# MBR.net
KiCad netlist of a schematic drawn in Altium Designer
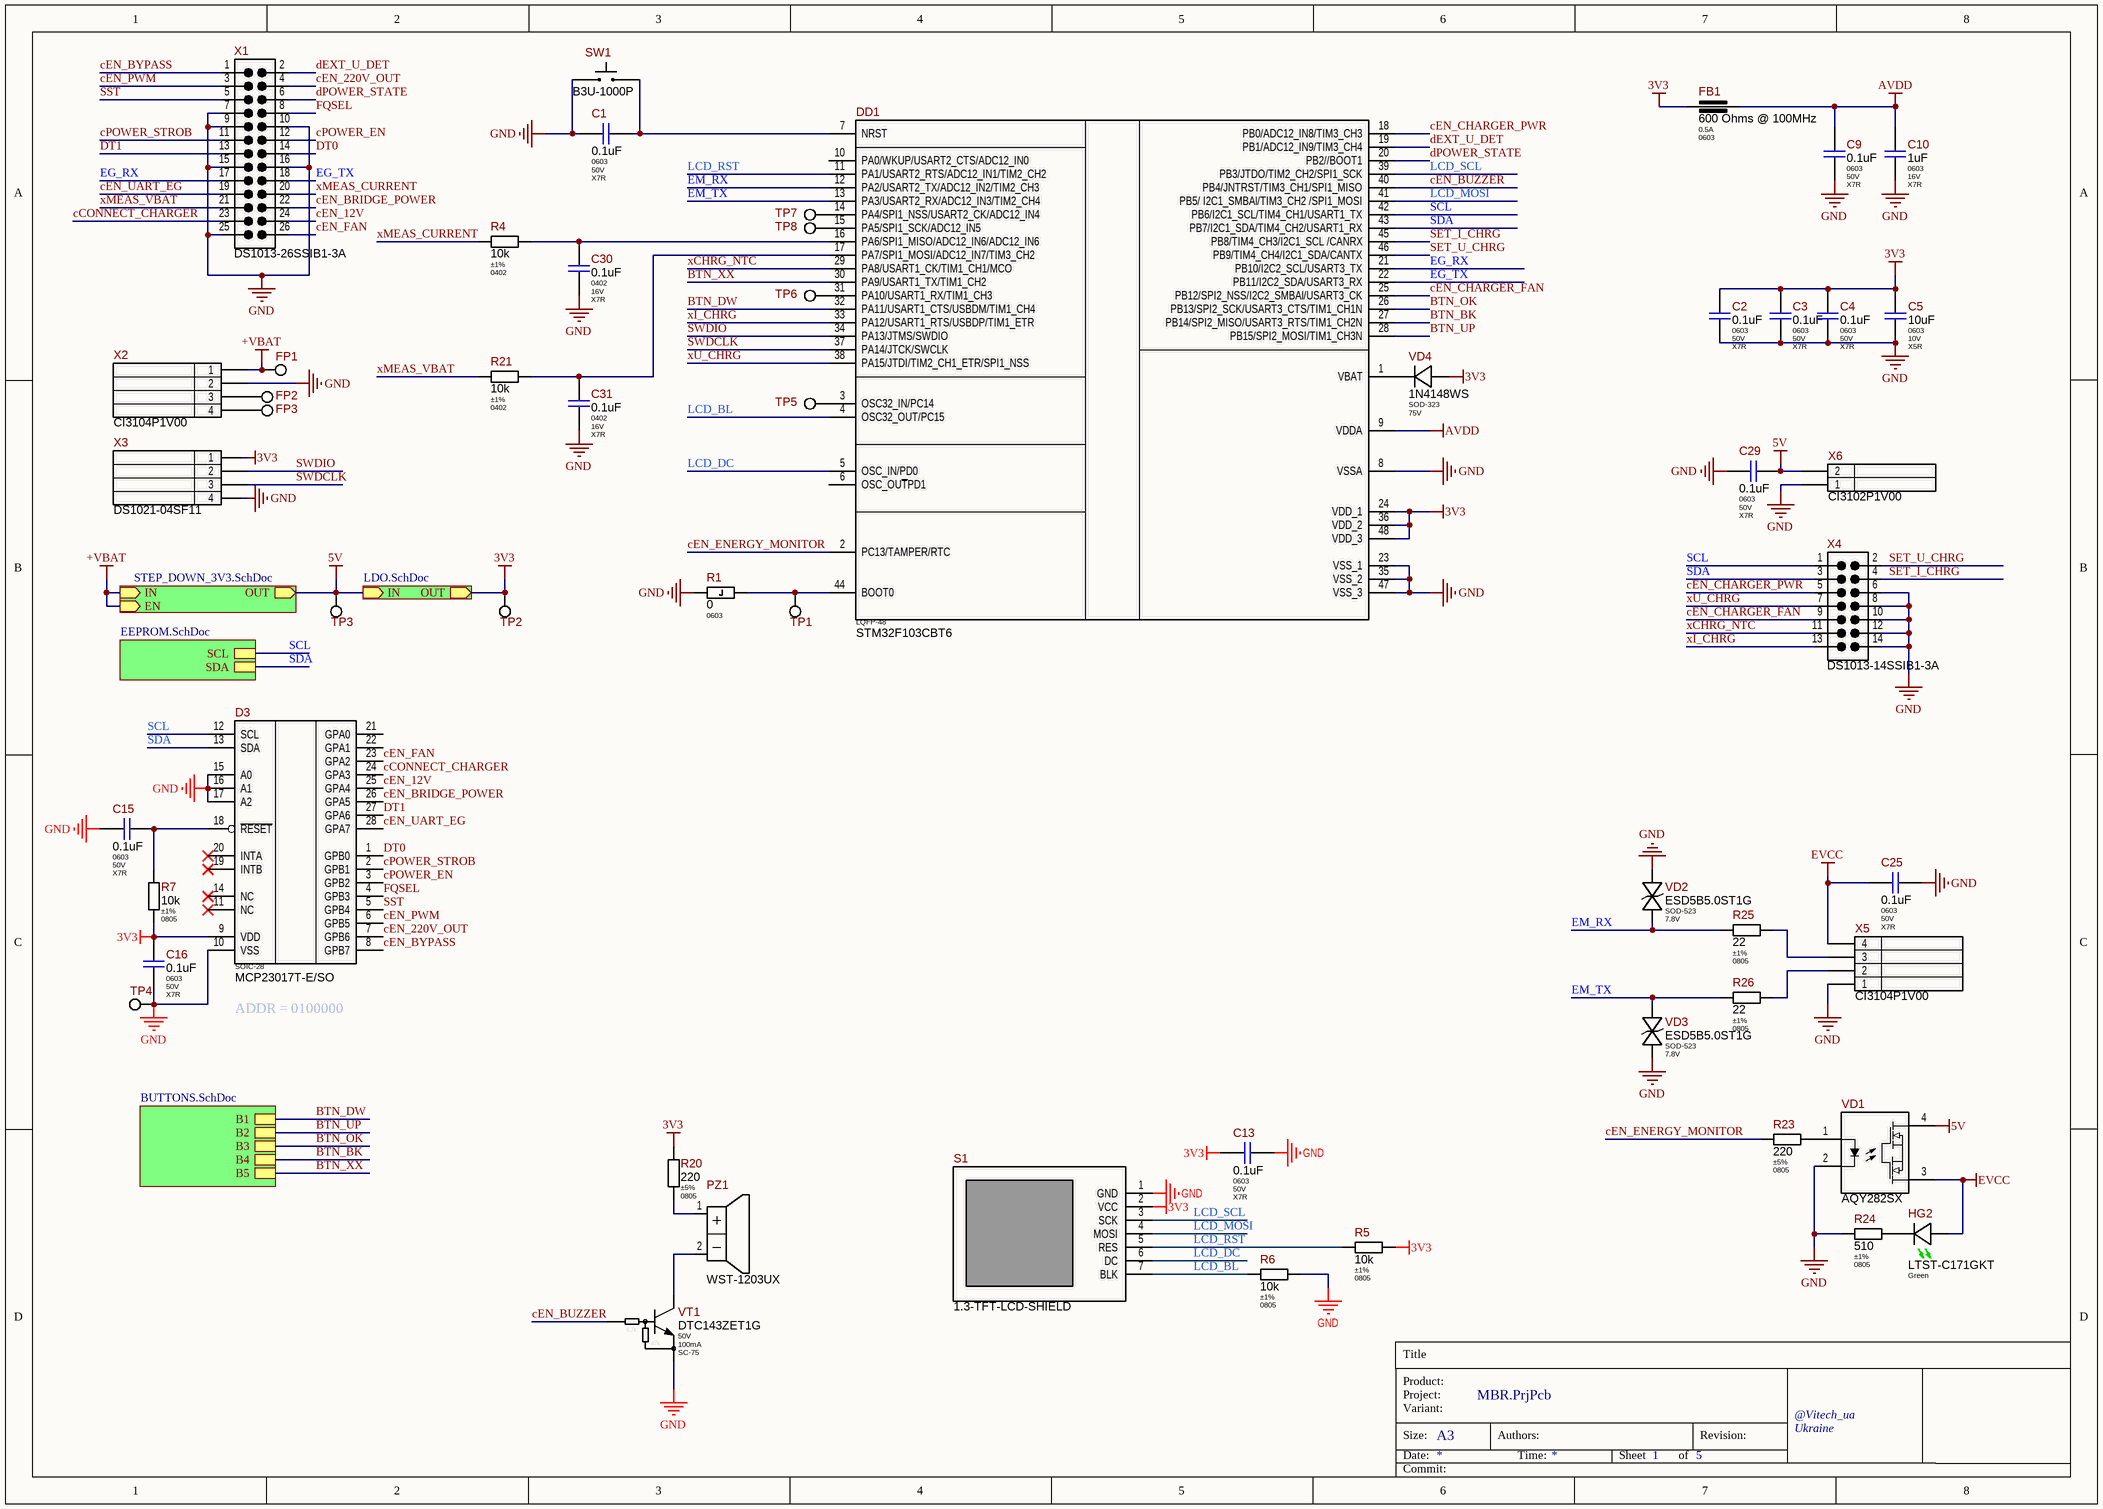
[diagram p0: MBR.SchDoc]

(export (version "E")
  (design (tool "Eeschema 10.0.6"))
  (components
    (comp (ref "C1")
      (value "0.1uF")
      (footprint "C_CERAMIC_0603_MED")
      (description "100nF 50V X7R ±10% 0603 Ceramic Capacitor RoHS")
      (fields
        (field (name "PACKAGE") "0603")
        (field (name "VOLTAGE") "50V")
        (field (name "DIELECTRIC TYPE") "X7R")
        (field (name "PART NUMBER") "CL10B104KB8NNND")
        (field (name "MANUFACTURER") "Samsung Electro-Mechanics")
      )
      (libsource (lib "capacitors") (part "CL10B104KB8NNND"))
    )
    (comp (ref "C2")
      (value "0.1uF")
      (footprint "C_CERAMIC_0603_MED")
      (description "100nF 50V X7R ±10% 0603 Ceramic Capacitor RoHS")
      (fields
        (field (name "PACKAGE") "0603")
        (field (name "VOLTAGE") "50V")
        (field (name "DIELECTRIC TYPE") "X7R")
        (field (name "PART NUMBER") "CL10B104KB8NNND")
        (field (name "MANUFACTURER") "Samsung Electro-Mechanics")
      )
      (libsource (lib "capacitors") (part "CL10B104KB8NNND"))
    )
    (comp (ref "C3")
      (value "0.1uF")
      (footprint "C_CERAMIC_0603_MED")
      (description "100nF 50V X7R ±10% 0603 Ceramic Capacitor RoHS")
      (fields
        (field (name "PACKAGE") "0603")
        (field (name "VOLTAGE") "50V")
        (field (name "DIELECTRIC TYPE") "X7R")
        (field (name "PART NUMBER") "CL10B104KB8NNND")
        (field (name "MANUFACTURER") "Samsung Electro-Mechanics")
      )
      (libsource (lib "capacitors") (part "CL10B104KB8NNND"))
    )
    (comp (ref "C4")
      (value "0.1uF")
      (footprint "C_CERAMIC_0603_MED")
      (description "100nF 50V X7R ±10% 0603 Ceramic Capacitor RoHS")
      (fields
        (field (name "PACKAGE") "0603")
        (field (name "VOLTAGE") "50V")
        (field (name "DIELECTRIC TYPE") "X7R")
        (field (name "PART NUMBER") "CL10B104KB8NNND")
        (field (name "MANUFACTURER") "Samsung Electro-Mechanics")
      )
      (libsource (lib "capacitors") (part "CL10B104KB8NNND"))
    )
    (comp (ref "C5")
      (value "10uF")
      (footprint "C_CERAMIC_0603_MED")
      (description "10uF 10V X5R ±10% 0603 Ceramic Capacitor RoHS")
      (fields
        (field (name "PACKAGE") "0603")
        (field (name "VOLTAGE") "10V")
        (field (name "DIELECTRIC TYPE") "X5R")
        (field (name "PART NUMBER") "CL10A106KP8NNNC")
        (field (name "MANUFACTURER") "Samsung Electro-Mechanics")
      )
      (libsource (lib "capacitors") (part "CL10A106KP8NNNC"))
    )
    (comp (ref "C9")
      (value "0.1uF")
      (footprint "C_CERAMIC_0603_MED")
      (description "100nF 50V X7R ±10% 0603 Ceramic Capacitor RoHS")
      (fields
        (field (name "PACKAGE") "0603")
        (field (name "VOLTAGE") "50V")
        (field (name "DIELECTRIC TYPE") "X7R")
        (field (name "PART NUMBER") "CL10B104KB8NNND")
        (field (name "MANUFACTURER") "Samsung Electro-Mechanics")
      )
      (libsource (lib "capacitors") (part "CL10B104KB8NNND"))
    )
    (comp (ref "C10")
      (value "1uF")
      (footprint "C_CERAMIC_0603_MED")
      (description "1uF 16V X7R ±10% 0603 Ceramic Capacitor RoHS")
      (fields
        (field (name "PACKAGE") "0603")
        (field (name "VOLTAGE") "16V")
        (field (name "DIELECTRIC TYPE") "X7R")
        (field (name "PART NUMBER") "CL10B105KO8NNNC")
        (field (name "MANUFACTURER") "Samsung Electro-Mechanics")
      )
      (libsource (lib "capacitors") (part "CL10B105KO8NNNC"))
    )
    (comp (ref "C13")
      (value "0.1uF")
      (footprint "C_CERAMIC_0603_MED")
      (description "100nF 50V X7R ±10% 0603 Ceramic Capacitor RoHS")
      (fields
        (field (name "PACKAGE") "0603")
        (field (name "VOLTAGE") "50V")
        (field (name "DIELECTRIC TYPE") "X7R")
        (field (name "PART NUMBER") "CL10B104KB8NNND")
        (field (name "MANUFACTURER") "Samsung Electro-Mechanics")
      )
      (libsource (lib "capacitors") (part "CL10B104KB8NNND"))
    )
    (comp (ref "C15")
      (value "0.1uF")
      (footprint "C_CERAMIC_0603_MED")
      (description "100nF 50V X7R ±10% 0603 Ceramic Capacitor RoHS")
      (fields
        (field (name "PACKAGE") "0603")
        (field (name "VOLTAGE") "50V")
        (field (name "DIELECTRIC TYPE") "X7R")
        (field (name "PART NUMBER") "CL10B104KB8NNND")
        (field (name "MANUFACTURER") "Samsung Electro-Mechanics")
      )
      (libsource (lib "capacitors") (part "CL10B104KB8NNND"))
    )
    (comp (ref "C16")
      (value "0.1uF")
      (footprint "C_CERAMIC_0603_MED")
      (description "100nF 50V X7R ±10% 0603 Ceramic Capacitor RoHS")
      (fields
        (field (name "PACKAGE") "0603")
        (field (name "VOLTAGE") "50V")
        (field (name "DIELECTRIC TYPE") "X7R")
        (field (name "PART NUMBER") "CL10B104KB8NNND")
        (field (name "MANUFACTURER") "Samsung Electro-Mechanics")
      )
      (libsource (lib "capacitors") (part "CL10B104KB8NNND"))
    )
    (comp (ref "C25")
      (value "0.1uF")
      (footprint "C_CERAMIC_0603_MED")
      (description "100nF 50V X7R ±10% 0603 Ceramic Capacitor RoHS")
      (fields
        (field (name "PACKAGE") "0603")
        (field (name "VOLTAGE") "50V")
        (field (name "DIELECTRIC TYPE") "X7R")
        (field (name "PART NUMBER") "CL10B104KB8NNND")
        (field (name "MANUFACTURER") "Samsung Electro-Mechanics")
      )
      (libsource (lib "capacitors") (part "CL10B104KB8NNND"))
    )
    (comp (ref "C29")
      (value "0.1uF")
      (footprint "C_CERAMIC_0603_MED")
      (description "100nF 50V X7R ±10% 0603 Ceramic Capacitor RoHS")
      (fields
        (field (name "PACKAGE") "0603")
        (field (name "VOLTAGE") "50V")
        (field (name "DIELECTRIC TYPE") "X7R")
        (field (name "PART NUMBER") "CL10B104KB8NNND")
        (field (name "MANUFACTURER") "Samsung Electro-Mechanics")
      )
      (libsource (lib "capacitors") (part "CL10B104KB8NNND"))
    )
    (comp (ref "C30")
      (value "0.1uF")
      (footprint "C_CERAMIC_0402_MED")
      (description "100nF 16V X7R ±5% 0402 Ceramic Capacitor RoHS")
      (fields
        (field (name "PACKAGE") "0402")
        (field (name "VOLTAGE") "16V")
        (field (name "DIELECTRIC TYPE") "X7R")
        (field (name "PART NUMBER") "CC0402JRX7R7BB104")
        (field (name "MANUFACTURER") "Yageo")
      )
      (libsource (lib "capacitors") (part "CC0402JRX7R7BB104"))
    )
    (comp (ref "C31")
      (value "0.1uF")
      (footprint "C_CERAMIC_0402_MED")
      (description "100nF 16V X7R ±5% 0402 Ceramic Capacitor RoHS")
      (fields
        (field (name "PACKAGE") "0402")
        (field (name "VOLTAGE") "16V")
        (field (name "DIELECTRIC TYPE") "X7R")
        (field (name "PART NUMBER") "CC0402JRX7R7BB104")
        (field (name "MANUFACTURER") "Yageo")
      )
      (libsource (lib "capacitors") (part "CC0402JRX7R7BB104"))
    )
    (comp (ref "D3")
      (value "MCP23017T-E/SO")
      (footprint "SOIC-28N_N")
      (description "I/O Expander 16 I2C 1.7MHz, SOIC-28")
      (fields
        (field (name "PACKAGE") "SOIC-28")
        (field (name "PART NUMBER") "MCP23017T-E/SO")
        (field (name "MANUFACTURER") "Microchip Technology")
      )
      (libsource (lib "ic") (part "MCP23017T-E/SO"))
    )
    (comp (ref "DD1")
      (value "STM32F103CBT6")
      (footprint "LQFP-48")
      (description "ARM Cortex-M3 MCU with 128 kB Flash, 72 MHz CPU, USB and CAN, LQFP-48")
      (fields
        (field (name "PACKAGE") "LQFP-48")
        (field (name "PART NUMBER") "STM32F103CBT6")
        (field (name "MANUFACTURER") "STMicroelectronics")
      )
      (libsource (lib "ic") (part "STM32F103CBT6"))
    )
    (comp (ref "FB1")
      (value "600 Ohms @ 100MHz")
      (footprint "BLM18KGxxxBH1x_MED")
      (description "600 Ohms @ 100MHz Power Line Ferrite Bead 0603, 500mA 150mOhm")
      (fields
        (field (name "CURRENT") "0.5A")
        (field (name "PACKAGE") "0603")
        (field (name "PART NUMBER") "BLM18KG601BH1D")
        (field (name "TOLERANCE") "±25%")
      )
      (libsource (lib "inductors") (part "BLM18KG601BH1D"))
    )
    (comp (ref "FP1")
      (value "PAD-1.75mm")
      (footprint "PAD-1.75mm")
      (description "1.75mm Pad for Plug-In or Receptacle")
      (fields (field (name "MANUFACTURER") "NONE"))
      (libsource (lib "probetools") (part "PAD-1.75mm"))
    )
    (comp (ref "FP2")
      (value "PAD-1.75mm")
      (footprint "PAD-1.75mm")
      (description "1.75mm Pad for Plug-In or Receptacle")
      (fields (field (name "MANUFACTURER") "NONE"))
      (libsource (lib "probetools") (part "PAD-1.75mm"))
    )
    (comp (ref "FP3")
      (value "PAD-1.75mm")
      (footprint "PAD-1.75mm")
      (description "1.75mm Pad for Plug-In or Receptacle")
      (fields (field (name "MANUFACTURER") "NONE"))
      (libsource (lib "probetools") (part "PAD-1.75mm"))
    )
    (comp (ref "HG2")
      (value "LTST-C171GKT")
      (footprint "LTST-C171GKT")
      (description "Low Power LED, Green 565nm, Clear, SMD 0805, Vf 2.1V - 2.6V, 5 ~ 12mcd @ 20 mA, 130°")
      (fields
        (field (name "PART NUMBER") "LTST-C171GKT")
        (field (name "COLOR") "Green")
        (field (name "MANUFACTURER") "Lite-On Optoelectronics")
      )
      (libsource (lib "opto") (part "LTST-C171GKT"))
    )
    (comp (ref "PZ1")
      (value "WST-1203UX")
      (footprint "WST-1203UX")
      (description "Buzzer, Internally Driven Magnetic 3V 30mA 2.3kHz 82dB @ 3V, 10cm, PTH")
      (fields (field (name "PART NUMBER") "WST-1203UX") (field (name "MANUFACTURER") "Soberton"))
      (libsource (lib "misc") (part "WST-1203UX"))
    )
    (comp (ref "R1")
      (value "0")
      (footprint "R_ANY_CHIP_0603_MED")
      (description "0 Ohms Jumper, 1/10W 0603 Thick Film Resistor")
      (fields
        (field (name "TOLERANCE") "±5%")
        (field (name "PACKAGE") "0603")
        (field (name "PART NUMBER") "RC0603JR-070RL")
      )
      (libsource (lib "resistors") (part "RC0603JR-070RL"))
    )
    (comp (ref "R4")
      (value "10k")
      (footprint "R_ANY_CHIP_0402_MED")
      (description "10 kOhms ±1% 1/16W 0402 Thick Film Resistor")
      (fields
        (field (name "TOLERANCE") "±1%")
        (field (name "PACKAGE") "0402")
        (field (name "PART NUMBER") "RC0402FR-0710KL")
        (field (name "MANUFACTURER") "Yageo")
      )
      (libsource (lib "resistors") (part "RC0402FR-0710KL"))
    )
    (comp (ref "R5")
      (value "10k")
      (footprint "R_ANY_CHIP_0805_MED")
      (description "10 kOhms ±1%, 1/8W 0805 Thick Film Resistor")
      (fields
        (field (name "TOLERANCE") "±1%")
        (field (name "PACKAGE") "0805")
        (field (name "PART NUMBER") "RC0805FR-0710K2L")
        (field (name "MANUFACTURER") "Yageo")
      )
      (libsource (lib "resistors") (part "RC0805FR-0710K2L"))
    )
    (comp (ref "R6")
      (value "10k")
      (footprint "R_ANY_CHIP_0805_MED")
      (description "10 kOhms ±1%, 1/8W 0805 Thick Film Resistor")
      (fields
        (field (name "TOLERANCE") "±1%")
        (field (name "PACKAGE") "0805")
        (field (name "PART NUMBER") "RC0805FR-0710K2L")
        (field (name "MANUFACTURER") "Yageo")
      )
      (libsource (lib "resistors") (part "RC0805FR-0710K2L"))
    )
    (comp (ref "R7")
      (value "10k")
      (footprint "R_ANY_CHIP_0805_MED")
      (description "10 kOhms ±1%, 1/8W 0805 Thick Film Resistor")
      (fields
        (field (name "TOLERANCE") "±1%")
        (field (name "PACKAGE") "0805")
        (field (name "PART NUMBER") "RC0805FR-0710K2L")
        (field (name "MANUFACTURER") "Yageo")
      )
      (libsource (lib "resistors") (part "RC0805FR-0710K2L"))
    )
    (comp (ref "R20")
      (value "220")
      (footprint "R_ANY_CHIP_0805_MED")
      (description "220 Ohms ±5%, 1/8W 0805 Thick Film Resistor")
      (fields
        (field (name "TOLERANCE") "±5%")
        (field (name "PACKAGE") "0805")
        (field (name "PART NUMBER") "RC0805JR-07220RL")
        (field (name "MANUFACTURER") "Yageo")
      )
      (libsource (lib "resistors") (part "RC0805JR-07220RL"))
    )
    (comp (ref "R21")
      (value "10k")
      (footprint "R_ANY_CHIP_0402_MED")
      (description "10 kOhms ±1% 1/16W 0402 Thick Film Resistor")
      (fields
        (field (name "TOLERANCE") "±1%")
        (field (name "PACKAGE") "0402")
        (field (name "PART NUMBER") "RC0402FR-0710KL")
        (field (name "MANUFACTURER") "Yageo")
      )
      (libsource (lib "resistors") (part "RC0402FR-0710KL"))
    )
    (comp (ref "R23")
      (value "220")
      (footprint "R_ANY_CHIP_0805_MED")
      (description "220 Ohms ±5%, 1/8W 0805 Thick Film Resistor")
      (fields
        (field (name "TOLERANCE") "±5%")
        (field (name "PACKAGE") "0805")
        (field (name "PART NUMBER") "RC0805JR-07220RL")
        (field (name "MANUFACTURER") "Yageo")
      )
      (libsource (lib "resistors") (part "RC0805JR-07220RL"))
    )
    (comp (ref "R24")
      (value "510")
      (footprint "R_ANY_CHIP_0805_MED")
      (description "510 Ohms ±1%, 1/2W 0805 High Power Thick Film Resistor")
      (fields
        (field (name "TOLERANCE") "±1%")
        (field (name "PACKAGE") "0805")
        (field (name "PART NUMBER") "ERJ-P06F5100V")
        (field (name "MANUFACTURER") "Panasonic")
      )
      (libsource (lib "resistors") (part "ERJ-P06F5100V"))
    )
    (comp (ref "R25")
      (value "22")
      (footprint "R_ANY_CHIP_0805_MED")
      (description "22 Ohms ±1%, 1/8W 0805 Thick Film Resistor")
      (fields
        (field (name "TOLERANCE") "±1%")
        (field (name "PACKAGE") "0805")
        (field (name "PART NUMBER") "RC0805FR-0722RL")
        (field (name "MANUFACTURER") "Yageo")
      )
      (libsource (lib "resistors") (part "RC0805FR-0722RL"))
    )
    (comp (ref "R26")
      (value "22")
      (footprint "R_ANY_CHIP_0805_MED")
      (description "22 Ohms ±1%, 1/8W 0805 Thick Film Resistor")
      (fields
        (field (name "TOLERANCE") "±1%")
        (field (name "PACKAGE") "0805")
        (field (name "PART NUMBER") "RC0805FR-0722RL")
        (field (name "MANUFACTURER") "Yageo")
      )
      (libsource (lib "resistors") (part "RC0805FR-0722RL"))
    )
    (comp (ref "S1")
      (value "1.3-LCD-Shield")
      (footprint "1.3-TFT-LCD-SHIELD")
      (description "1.3 Inch SPI TFT LCD Module, ST7789 Controller")
      (fields (field (name "MANUFACTURER") "Undefined") (field (name "PART NUMBER") "1.3-TFT-LCD-SHIELD"))
      (libsource (lib "modules") (part "1.3-TFT-LCD-SHIELD"))
    )
    (comp (ref "SW1")
      (value "B3U-1000P")
      (footprint "B3U-1000P")
      (description "Tactile Switch SPST-NO SMD, 153gf, Height 1.6mm")
      (fields (field (name "PART NUMBER") "B3U-1000P") (field (name "MANUFACTURER") "Omron"))
      (libsource (lib "electromechanicals") (part "B3U-1000P"))
    )
    (comp (ref "TP1")
      (value "PAD-0.96mm")
      (footprint "PAD-0.96mm")
      (description "0.96mm Pad for Plug-In or Receptacle")
      (fields (field (name "MANUFACTURER") "NONE"))
      (libsource (lib "probetools") (part "PAD-0.96mm"))
    )
    (comp (ref "TP2")
      (value "PAD-0.96mm")
      (footprint "PAD-0.96mm")
      (description "0.96mm Pad for Plug-In or Receptacle")
      (fields (field (name "MANUFACTURER") "NONE"))
      (libsource (lib "probetools") (part "PAD-0.96mm"))
    )
    (comp (ref "TP3")
      (value "PAD-0.96mm")
      (footprint "PAD-0.96mm")
      (description "0.96mm Pad for Plug-In or Receptacle")
      (fields (field (name "MANUFACTURER") "NONE"))
      (libsource (lib "probetools") (part "PAD-0.96mm"))
    )
    (comp (ref "TP4")
      (value "PAD-0.96mm")
      (footprint "PAD-0.96mm")
      (description "0.96mm Pad for Plug-In or Receptacle")
      (fields (field (name "MANUFACTURER") "NONE"))
      (libsource (lib "probetools") (part "PAD-0.96mm"))
    )
    (comp (ref "TP5")
      (value "PAD-0.96mm")
      (footprint "PAD-0.96mm")
      (description "0.96mm Pad for Plug-In or Receptacle")
      (fields (field (name "MANUFACTURER") "NONE"))
      (libsource (lib "probetools") (part "PAD-0.96mm"))
    )
    (comp (ref "TP6")
      (value "PAD-0.96mm")
      (footprint "PAD-0.96mm")
      (description "0.96mm Pad for Plug-In or Receptacle")
      (fields (field (name "MANUFACTURER") "NONE"))
      (libsource (lib "probetools") (part "PAD-0.96mm"))
    )
    (comp (ref "TP7")
      (value "PAD-0.96mm")
      (footprint "PAD-0.96mm")
      (description "0.96mm Pad for Plug-In or Receptacle")
      (fields (field (name "MANUFACTURER") "NONE"))
      (libsource (lib "probetools") (part "PAD-0.96mm"))
    )
    (comp (ref "TP8")
      (value "PAD-0.96mm")
      (footprint "PAD-0.96mm")
      (description "0.96mm Pad for Plug-In or Receptacle")
      (fields (field (name "MANUFACTURER") "NONE"))
      (libsource (lib "probetools") (part "PAD-0.96mm"))
    )
    (comp (ref "VD1")
      (value "AQY282SX")
      (footprint "SOP-4N")
      (description "PhotoMOS Solid State Relay, SPST-NO, 0-60V, 0.5A, 2.5Ohm Max, SOP-4")
      (fields
        (field (name "PART NUMBER") "AQY282SX")
        (field (name "MANUFACTURER") "Panasonic Electric Works")
      )
      (libsource (lib "opto") (part "AQY282SX"))
    )
    (comp (ref "VD2")
      (value "ESD5B5.0ST1G")
      (footprint "SOD-523F-Bi1_MED")
      (description "Bidirectional ESD Protection Diode, 5V Working Voltage, 32pF, SOD-523")
      (fields
        (field (name "PART NUMBER") "ESD5B5.0ST1G")
        (field (name "PACKAGE") "SOD-523")
        (field (name "VOLTAGE") "7.8V")
        (field (name "MANUFACTURER") "Onsemi")
      )
      (libsource (lib "diodes") (part "ESD5B5.0ST1G"))
    )
    (comp (ref "VD3")
      (value "ESD5B5.0ST1G")
      (footprint "SOD-523F-Bi1_MED")
      (description "Bidirectional ESD Protection Diode, 5V Working Voltage, 32pF, SOD-523")
      (fields
        (field (name "PART NUMBER") "ESD5B5.0ST1G")
        (field (name "PACKAGE") "SOD-523")
        (field (name "VOLTAGE") "7.8V")
        (field (name "MANUFACTURER") "Onsemi")
      )
      (libsource (lib "diodes") (part "ESD5B5.0ST1G"))
    )
    (comp (ref "VD4")
      (value "1N4148WS")
      (footprint "SOD-323_MED")
      (description "Diode Standard 75V 150mA, SOD-323F")
      (fields
        (field (name "MANUFACTURER") "Diodec Semiconductor")
        (field (name "PART NUMBER") "1N4148WS")
        (field (name "PACKAGE") "SOD-323")
        (field (name "VOLTAGE") "75V")
      )
      (libsource (lib "diodes") (part "1N4148WS"))
    )
    (comp (ref "VT1")
      (value "DTC143ZET1G")
      (footprint "SOT-416")
      (description "50V, 100mA Low Vce(sat) NPN Digital Transistor, Pre-Biased 4.7k/47k (with built-in resistors)")
      (fields
        (field (name "PART NUMBER") "DTC143ZET1G")
        (field (name "VCE") "50V")
        (field (name "IC") "100mA")
        (field (name "PACKAGE") "SC-75")
        (field (name "MANUFACTURER") "Onsemi")
      )
      (libsource (lib "transistors") (part "DTC143ZET1G"))
    )
    (comp (ref "X1")
      (value "DS1013-26SSIB1-3A")
      (footprint "BH-26")
      (description "2.54mm Vertical Box Header, Two Rows, 26 Pin, 20mOhm max, Male IDC BH-26")
      (fields (field (name "PART NUMBER") "DS1013-26SSIB1-3A") (field (name "MANUFACTURER") "Connfly"))
      (libsource (lib "connectors") (part "DS1013-26SSIB1-3A"))
    )
    (comp (ref "X2")
      (value "WH-04S")
      (footprint "WF-4S")
      (description "WH Series 2.54mm Wire to Board Straight DIP Type Headers, 4 Pin")
      (fields (field (name "PART NUMBER") "CI3104P1V00") (field (name "MANUFACTURER") "CviLux"))
      (libsource (lib "connectors") (part "CI3104P1V00"))
    )
    (comp (ref "X3")
      (value "PLS-4 (Part of PLS-40)")
      (footprint "DS1021-04S")
      (description "4 Pin 2.54mm Male Header, Vertical, 3mm and 6.1mm, PLS-4")
      (fields (field (name "PART NUMBER") "DS1021-04SF11") (field (name "MANUFACTURER") "Connfly"))
      (libsource (lib "connectors") (part "DS1021-04SF11"))
    )
    (comp (ref "X4")
      (value "DS1013-14SSIB1-3A")
      (footprint "BH-14")
      (description "2.54mm Streight Box Header, Two Rows, 14 Pin, 20mOhm max, Male IDC BH-14")
      (fields (field (name "PART NUMBER") "DS1013-14SSIB1-3A") (field (name "MANUFACTURER") "Connfly"))
      (libsource (lib "connectors") (part "DS1013-14SSIB1-3A"))
    )
    (comp (ref "X5")
      (value "WH-04S")
      (footprint "WF-4S")
      (description "WH Series 2.54mm Wire to Board Straight DIP Type Headers, 4 Pin")
      (fields (field (name "PART NUMBER") "CI3104P1V00") (field (name "MANUFACTURER") "CviLux"))
      (libsource (lib "") (part "CI3104P1V00_1"))
    )
    (comp (ref "X6")
      (value "WH-02S")
      (footprint "WF-2S")
      (description "WH Series 2.54mm Wire to Board Straight DIP Type Headers, 2 Pin")
      (fields (field (name "PART NUMBER") "CI3102P1V00") (field (name "MANUFACTURER") "CviLux"))
      (libsource (lib "connectors") (part "CI3102P1V00"))
    )
  )
  (nets
    (net (code "1") (name "+VBAT") (class "Default")
      (node (ref "FP1") (pin "1") (pintype "passive"))
      (node (ref "X2") (pin "1") (pinfunction "1_1") (pintype "passive"))
    )
    (net (code "2") (name "/BTN_BK") (class "Default")
      (node (ref "DD1") (pin "27") (pinfunction "PB14/SPI2_MISO/USART3_RTS/TIM1_CH2N_27") (pintype "passive"))
    )
    (net (code "3") (name "/BTN_DW") (class "Default")
      (node (ref "DD1") (pin "32") (pinfunction "PA11/USART1_CTS/USBDM/TIM1_CH4_32") (pintype "passive"))
    )
    (net (code "4") (name "/BTN_OK") (class "Default")
      (node (ref "DD1") (pin "26") (pinfunction "PB13/SPI2_SCK/USART3_CTS/TIM1_CH1N_26") (pintype "passive"))
    )
    (net (code "5") (name "/BTN_UP") (class "Default")
      (node (ref "DD1") (pin "28") (pinfunction "PB15/SPI2_MOSI/TIM1_CH3N_28") (pintype "passive"))
    )
    (net (code "6") (name "/BTN_XX") (class "Default")
      (node (ref "DD1") (pin "30") (pinfunction "PA9/USART1_TX/TIM1_CH2_30") (pintype "passive"))
    )
    (net (code "7") (name "/DT0") (class "Default")
      (node (ref "D3") (pin "1") (pinfunction "GPB0_1") (pintype "passive"))
      (node (ref "X1") (pin "14") (pintype "passive"))
    )
    (net (code "8") (name "/DT1") (class "Default")
      (node (ref "D3") (pin "27") (pinfunction "GPA6_27") (pintype "passive"))
      (node (ref "X1") (pin "13") (pintype "passive"))
    )
    (net (code "9") (name "/EG_RX") (class "Default")
      (node (ref "DD1") (pin "21") (pinfunction "PB10/I2C2_SCL/USART3_TX_21") (pintype "passive"))
      (node (ref "X1") (pin "17") (pintype "passive"))
    )
    (net (code "10") (name "/EG_TX") (class "Default")
      (node (ref "DD1") (pin "22") (pinfunction "PB11/I2C2_SDA/USART3_RX_22") (pintype "passive"))
      (node (ref "X1") (pin "18") (pintype "passive"))
    )
    (net (code "11") (name "/EM_RX") (class "Default")
      (node (ref "DD1") (pin "12") (pinfunction "PA2/USART2_TX/ADC12_IN2/TIM2_CH3_12") (pintype "passive"))
      (node (ref "R25") (pin "1") (pintype "passive"))
      (node (ref "VD2") (pin "AN1") (pinfunction "AN1_AN1") (pintype "passive"))
    )
    (net (code "12") (name "/EM_TX") (class "Default")
      (node (ref "DD1") (pin "13") (pinfunction "PA3/USART2_RX/ADC12_IN3/TIM2_CH4_13") (pintype "passive"))
      (node (ref "R26") (pin "1") (pintype "passive"))
      (node (ref "VD3") (pin "AN2") (pinfunction "AN2_AN2") (pintype "passive"))
    )
    (net (code "13") (name "/FQSEL") (class "Default")
      (node (ref "D3") (pin "4") (pinfunction "GPB3_4") (pintype "passive"))
      (node (ref "X1") (pin "8") (pintype "passive"))
    )
    (net (code "14") (name "/LCD_BL") (class "Default")
      (node (ref "DD1") (pin "4") (pinfunction "OSC32_OUT/PC15_4") (pintype "passive"))
      (node (ref "R6") (pin "1") (pintype "passive"))
      (node (ref "S1") (pin "7") (pinfunction "BLK_7") (pintype "passive"))
    )
    (net (code "15") (name "/LCD_DC") (class "Default")
      (node (ref "DD1") (pin "5") (pinfunction "OSC_IN/PD0_5") (pintype "passive"))
      (node (ref "S1") (pin "6") (pinfunction "DC_6") (pintype "passive"))
    )
    (net (code "16") (name "/LCD_MOSI") (class "Default")
      (node (ref "DD1") (pin "41") (pinfunction "PB5/_I2C1_SMBAl/TIM3_CH2_/SPI1_MOSI_41") (pintype "passive"))
      (node (ref "S1") (pin "4") (pinfunction "MOSI_4") (pintype "passive"))
    )
    (net (code "17") (name "/LCD_RST") (class "Default")
      (node (ref "DD1") (pin "11") (pinfunction "PA1/USART2_RTS/ADC12_IN1/TIM2_CH2_11") (pintype "passive"))
      (node (ref "R5") (pin "1") (pintype "passive"))
      (node (ref "S1") (pin "5") (pinfunction "RES_5") (pintype "passive"))
    )
    (net (code "18") (name "/LCD_SCL") (class "Default")
      (node (ref "DD1") (pin "39") (pinfunction "PB3/JTDO/TIM2_CH2/SPI1_SCK_39") (pintype "passive"))
      (node (ref "S1") (pin "3") (pinfunction "SCK_3") (pintype "passive"))
    )
    (net (code "19") (name "/SCL") (class "Default")
      (node (ref "D3") (pin "12") (pinfunction "SCL_12") (pintype "passive"))
      (node (ref "DD1") (pin "42") (pinfunction "PB6/I2C1_SCL/TIM4_CH1/USART1_TX_42") (pintype "passive"))
      (node (ref "X4") (pin "1") (pintype "passive"))
    )
    (net (code "20") (name "/SDA") (class "Default")
      (node (ref "D3") (pin "13") (pinfunction "SDA_13") (pintype "passive"))
      (node (ref "DD1") (pin "43") (pinfunction "PB7/I2C1_SDA/TIM4_CH2/USART1_RX_43") (pintype "passive"))
      (node (ref "X4") (pin "3") (pintype "passive"))
    )
    (net (code "21") (name "/SET_I_CHRG") (class "Default")
      (node (ref "DD1") (pin "45") (pinfunction "PB8/TIM4_CH3/I2C1_SCL_/CANRX_45") (pintype "passive"))
      (node (ref "X4") (pin "4") (pintype "passive"))
    )
    (net (code "22") (name "/SET_U_CHRG") (class "Default")
      (node (ref "DD1") (pin "46") (pinfunction "PB9/TIM4_CH4/I2C1_SDA/CANTX_46") (pintype "passive"))
      (node (ref "X4") (pin "2") (pintype "passive"))
    )
    (net (code "23") (name "/SST") (class "Default")
      (node (ref "D3") (pin "5") (pinfunction "GPB4_5") (pintype "passive"))
      (node (ref "X1") (pin "5") (pintype "passive"))
    )
    (net (code "24") (name "/SWDCLK") (class "Default")
      (node (ref "DD1") (pin "37") (pinfunction "PA14/JTCK/SWCLK_37") (pintype "passive"))
      (node (ref "X3") (pin "3") (pinfunction "3_3") (pintype "passive"))
    )
    (net (code "25") (name "/SWDIO") (class "Default")
      (node (ref "DD1") (pin "34") (pinfunction "PA13/JTMS/SWDIO_34") (pintype "passive"))
      (node (ref "X3") (pin "2") (pinfunction "2_2") (pintype "passive"))
    )
    (net (code "26") (name "/cCONNECT_CHARGER") (class "Default")
      (node (ref "D3") (pin "24") (pinfunction "GPA3_24") (pintype "passive"))
      (node (ref "X1") (pin "23") (pintype "passive"))
    )
    (net (code "27") (name "/cEN_12V") (class "Default")
      (node (ref "D3") (pin "25") (pinfunction "GPA4_25") (pintype "passive"))
      (node (ref "X1") (pin "24") (pintype "passive"))
    )
    (net (code "28") (name "/cEN_220V_OUT") (class "Default")
      (node (ref "D3") (pin "7") (pinfunction "GPB6_7") (pintype "passive"))
      (node (ref "X1") (pin "4") (pintype "passive"))
    )
    (net (code "29") (name "/cEN_BRIDGE_POWER") (class "Default")
      (node (ref "D3") (pin "26") (pinfunction "GPA5_26") (pintype "passive"))
      (node (ref "X1") (pin "22") (pintype "passive"))
    )
    (net (code "30") (name "/cEN_BUZZER") (class "Default")
      (node (ref "DD1") (pin "40") (pinfunction "PB4/JNTRST/TIM3_CH1/SPI1_MISO_40") (pintype "passive"))
      (node (ref "VT1") (pin "1") (pinfunction "B_1") (pintype "passive"))
    )
    (net (code "31") (name "/cEN_BYPASS") (class "Default")
      (node (ref "D3") (pin "8") (pinfunction "GPB7_8") (pintype "passive"))
      (node (ref "X1") (pin "1") (pintype "passive"))
    )
    (net (code "32") (name "/cEN_CHARGER_FAN") (class "Default")
      (node (ref "DD1") (pin "25") (pinfunction "PB12/SPI2_NSS/I2C2_SMBAl/USART3_CK_25") (pintype "passive"))
      (node (ref "X4") (pin "9") (pintype "passive"))
    )
    (net (code "33") (name "/cEN_CHARGER_PWR") (class "Default")
      (node (ref "DD1") (pin "18") (pinfunction "PB0/ADC12_IN8/TIM3_CH3_18") (pintype "passive"))
      (node (ref "X4") (pin "5") (pintype "passive"))
    )
    (net (code "34") (name "/cEN_ENERGY_MONITOR") (class "Default")
      (node (ref "DD1") (pin "2") (pinfunction "PC13/TAMPER/RTC_2") (pintype "passive"))
      (node (ref "R23") (pin "2") (pintype "passive"))
    )
    (net (code "35") (name "/cEN_FAN") (class "Default")
      (node (ref "D3") (pin "23") (pinfunction "GPA2_23") (pintype "passive"))
      (node (ref "X1") (pin "26") (pintype "passive"))
    )
    (net (code "36") (name "/cEN_UART_EG") (class "Default")
      (node (ref "D3") (pin "28") (pinfunction "GPA7_28") (pintype "passive"))
      (node (ref "X1") (pin "19") (pintype "passive"))
    )
    (net (code "37") (name "/cPOWER_EN") (class "Default")
      (node (ref "D3") (pin "3") (pinfunction "GPB2_3") (pintype "passive"))
      (node (ref "X1") (pin "12") (pintype "passive"))
    )
    (net (code "38") (name "/cPOWER_STROB") (class "Default")
      (node (ref "D3") (pin "2") (pinfunction "GPB1_2") (pintype "passive"))
      (node (ref "X1") (pin "11") (pintype "passive"))
    )
    (net (code "39") (name "/dEXT_U_DET") (class "Default")
      (node (ref "DD1") (pin "19") (pinfunction "PB1/ADC12_IN9/TIM3_CH4_19") (pintype "passive"))
      (node (ref "X1") (pin "2") (pintype "passive"))
    )
    (net (code "40") (name "/dPOWER_STATE") (class "Default")
      (node (ref "DD1") (pin "20") (pinfunction "PB2//BOOT1_20") (pintype "passive"))
      (node (ref "X1") (pin "6") (pintype "passive"))
    )
    (net (code "41") (name "/xCHRG_NTC") (class "Default")
      (node (ref "DD1") (pin "29") (pinfunction "PA8/USART1_CK/TIM1_CH1/MCO_29") (pintype "passive"))
      (node (ref "X4") (pin "11") (pintype "passive"))
    )
    (net (code "42") (name "/xI_CHRG") (class "Default")
      (node (ref "DD1") (pin "33") (pinfunction "PA12/USART1_RTS/USBDP/TIM1_ETR_33") (pintype "passive"))
      (node (ref "X4") (pin "13") (pintype "passive"))
    )
    (net (code "43") (name "/xMEAS_CURRENT") (class "Default")
      (node (ref "R4") (pin "1") (pintype "passive"))
      (node (ref "X1") (pin "20") (pintype "passive"))
    )
    (net (code "44") (name "/xMEAS_VBAT") (class "Default")
      (node (ref "R21") (pin "1") (pintype "passive"))
      (node (ref "X1") (pin "21") (pintype "passive"))
    )
    (net (code "45") (name "/xU_CHRG") (class "Default")
      (node (ref "DD1") (pin "38") (pinfunction "PA15/JTDI/TIM2_CH1_ETR/SPI1_NSS_38") (pintype "passive"))
      (node (ref "X4") (pin "7") (pintype "passive"))
    )
    (net (code "46") (name "/сEN_PWM") (class "Default")
      (node (ref "D3") (pin "6") (pinfunction "GPB5_6") (pintype "passive"))
      (node (ref "X1") (pin "3") (pintype "passive"))
    )
    (net (code "47") (name "3V3") (class "Default")
      (node (ref "C13") (pin "2") (pinfunction "2_2") (pintype "passive"))
      (node (ref "C16") (pin "2") (pinfunction "2_2") (pintype "passive"))
      (node (ref "C2") (pin "2") (pinfunction "2_2") (pintype "passive"))
      (node (ref "C3") (pin "2") (pinfunction "2_2") (pintype "passive"))
      (node (ref "C4") (pin "2") (pinfunction "2_2") (pintype "passive"))
      (node (ref "C5") (pin "2") (pinfunction "2_2") (pintype "passive"))
      (node (ref "D3") (pin "9") (pinfunction "VDD_9") (pintype "passive"))
      (node (ref "DD1") (pin "24") (pinfunction "VDD_1_24") (pintype "passive"))
      (node (ref "DD1") (pin "36") (pinfunction "VDD_2_36") (pintype "passive"))
      (node (ref "DD1") (pin "48") (pinfunction "VDD_3_48") (pintype "passive"))
      (node (ref "FB1") (pin "2") (pintype "passive"))
      (node (ref "R20") (pin "2") (pintype "passive"))
      (node (ref "R5") (pin "2") (pintype "passive"))
      (node (ref "R7") (pin "1") (pintype "passive"))
      (node (ref "S1") (pin "2") (pinfunction "VCC_2") (pintype "passive"))
      (node (ref "TP2") (pin "1") (pintype "passive"))
      (node (ref "VD4") (pin "AN") (pintype "passive"))
      (node (ref "X3") (pin "1") (pinfunction "1_1") (pintype "passive"))
    )
    (net (code "48") (name "5V") (class "Default")
      (node (ref "C29") (pin "1") (pinfunction "1_1") (pintype "passive"))
      (node (ref "TP3") (pin "1") (pintype "passive"))
      (node (ref "VD1") (pin "4") (pinfunction "D1_4") (pintype "passive"))
      (node (ref "X6") (pin "2") (pinfunction "2_2") (pintype "passive"))
    )
    (net (code "49") (name "AVDD") (class "Default")
      (node (ref "C10") (pin "1") (pinfunction "1_1") (pintype "passive"))
      (node (ref "C9") (pin "2") (pinfunction "2_2") (pintype "passive"))
      (node (ref "DD1") (pin "9") (pinfunction "VDDA_9") (pintype "passive"))
      (node (ref "FB1") (pin "1") (pintype "passive"))
    )
    (net (code "50") (name "EVCC") (class "Default")
      (node (ref "C25") (pin "1") (pinfunction "1_1") (pintype "passive"))
      (node (ref "HG2") (pin "AN") (pinfunction "Anode_AN") (pintype "passive"))
      (node (ref "VD1") (pin "3") (pinfunction "D2_3") (pintype "passive"))
      (node (ref "X5") (pin "4") (pinfunction "4_4") (pintype "passive"))
    )
    (net (code "51") (name "GND") (class "Default")
      (node (ref "C1") (pin "2") (pinfunction "2_2") (pintype "passive"))
      (node (ref "C10") (pin "2") (pinfunction "2_2") (pintype "passive"))
      (node (ref "C13") (pin "1") (pinfunction "1_1") (pintype "passive"))
      (node (ref "C15") (pin "2") (pinfunction "2_2") (pintype "passive"))
      (node (ref "C16") (pin "1") (pinfunction "1_1") (pintype "passive"))
      (node (ref "C2") (pin "1") (pinfunction "1_1") (pintype "passive"))
      (node (ref "C25") (pin "2") (pinfunction "2_2") (pintype "passive"))
      (node (ref "C29") (pin "2") (pinfunction "2_2") (pintype "passive"))
      (node (ref "C3") (pin "1") (pinfunction "1_1") (pintype "passive"))
      (node (ref "C30") (pin "2") (pinfunction "2_2") (pintype "passive"))
      (node (ref "C31") (pin "2") (pinfunction "2_2") (pintype "passive"))
      (node (ref "C4") (pin "1") (pinfunction "1_1") (pintype "passive"))
      (node (ref "C5") (pin "1") (pinfunction "1_1") (pintype "passive"))
      (node (ref "C9") (pin "1") (pinfunction "1_1") (pintype "passive"))
      (node (ref "D3") (pin "10") (pinfunction "VSS_10") (pintype "passive"))
      (node (ref "D3") (pin "15") (pinfunction "A0_15") (pintype "passive"))
      (node (ref "D3") (pin "16") (pinfunction "A1_16") (pintype "passive"))
      (node (ref "D3") (pin "17") (pinfunction "A2_17") (pintype "passive"))
      (node (ref "DD1") (pin "23") (pinfunction "VSS_1_23") (pintype "passive"))
      (node (ref "DD1") (pin "35") (pinfunction "VSS_2_35") (pintype "passive"))
      (node (ref "DD1") (pin "47") (pinfunction "VSS_3_47") (pintype "passive"))
      (node (ref "DD1") (pin "8") (pinfunction "VSSA_8") (pintype "passive"))
      (node (ref "R1") (pin "2") (pintype "passive"))
      (node (ref "R24") (pin "1") (pintype "passive"))
      (node (ref "R6") (pin "2") (pintype "passive"))
      (node (ref "S1") (pin "1") (pinfunction "GND_1") (pintype "passive"))
      (node (ref "SW1") (pin "1") (pintype "passive"))
      (node (ref "TP4") (pin "1") (pintype "passive"))
      (node (ref "VD1") (pin "2") (pinfunction "Cathode_2") (pintype "passive"))
      (node (ref "VD2") (pin "AN2") (pinfunction "AN2_AN2") (pintype "passive"))
      (node (ref "VD3") (pin "AN1") (pinfunction "AN1_AN1") (pintype "passive"))
      (node (ref "VT1") (pin "2") (pinfunction "E_2") (pintype "passive"))
      (node (ref "X1") (pin "10") (pintype "passive"))
      (node (ref "X1") (pin "15") (pintype "passive"))
      (node (ref "X1") (pin "16") (pintype "passive"))
      (node (ref "X1") (pin "25") (pintype "passive"))
      (node (ref "X1") (pin "7") (pintype "passive"))
      (node (ref "X1") (pin "9") (pintype "passive"))
      (node (ref "X2") (pin "2") (pinfunction "2_2") (pintype "passive"))
      (node (ref "X3") (pin "4") (pinfunction "4_4") (pintype "passive"))
      (node (ref "X4") (pin "10") (pintype "passive"))
      (node (ref "X4") (pin "12") (pintype "passive"))
      (node (ref "X4") (pin "14") (pintype "passive"))
      (node (ref "X4") (pin "6") (pintype "passive"))
      (node (ref "X4") (pin "8") (pintype "passive"))
      (node (ref "X5") (pin "1") (pinfunction "1_1") (pintype "passive"))
      (node (ref "X6") (pin "1") (pinfunction "1_1") (pintype "passive"))
    )
    (net (code "52") (name "Net-(D3-~{RESET})") (class "Default")
      (node (ref "C15") (pin "1") (pinfunction "1_1") (pintype "passive"))
      (node (ref "D3") (pin "18") (pinfunction "~{RESET}_18") (pintype "passive"))
      (node (ref "R7") (pin "2") (pintype "passive"))
    )
    (net (code "53") (name "Net-(DD1-BOOT0)") (class "Default")
      (node (ref "DD1") (pin "44") (pinfunction "BOOT0_44") (pintype "passive"))
      (node (ref "R1") (pin "1") (pintype "passive"))
      (node (ref "TP1") (pin "1") (pintype "passive"))
    )
    (net (code "54") (name "Net-(DD1-NRST)") (class "Default")
      (node (ref "C1") (pin "1") (pinfunction "1_1") (pintype "passive"))
      (node (ref "DD1") (pin "7") (pinfunction "NRST_7") (pintype "passive"))
      (node (ref "SW1") (pin "2") (pintype "passive"))
    )
    (net (code "55") (name "Net-(DD1-OSC32_IN{slash}PC14)") (class "Default")
      (node (ref "DD1") (pin "3") (pinfunction "OSC32_IN/PC14_3") (pintype "passive"))
      (node (ref "TP5") (pin "1") (pintype "passive"))
    )
    (net (code "56") (name "Net-(DD1-PA4{slash}SPI1_NSS{slash}USART2_CK{slash}ADC12_IN4)") (class "Default")
      (node (ref "DD1") (pin "14") (pinfunction "PA4/SPI1_NSS/USART2_CK/ADC12_IN4_14") (pintype "passive"))
      (node (ref "TP7") (pin "1") (pintype "passive"))
    )
    (net (code "57") (name "Net-(DD1-PA5{slash}SPI1_SCK{slash}ADC12_IN5)") (class "Default")
      (node (ref "DD1") (pin "15") (pinfunction "PA5/SPI1_SCK/ADC12_IN5_15") (pintype "passive"))
      (node (ref "TP8") (pin "1") (pintype "passive"))
    )
    (net (code "58") (name "Net-(DD1-PA6{slash}SPI1_MISO{slash}ADC12_IN6{slash}ADC12_IN6)") (class "Default")
      (node (ref "C30") (pin "1") (pinfunction "1_1") (pintype "passive"))
      (node (ref "DD1") (pin "16") (pinfunction "PA6/SPI1_MISO/ADC12_IN6/ADC12_IN6_16") (pintype "passive"))
      (node (ref "R4") (pin "2") (pintype "passive"))
    )
    (net (code "59") (name "Net-(DD1-PA7{slash}SPI1_MOSI{slash}ADC12_IN7{slash}TIM3_CH2)") (class "Default")
      (node (ref "C31") (pin "1") (pinfunction "1_1") (pintype "passive"))
      (node (ref "DD1") (pin "17") (pinfunction "PA7/SPI1_MOSI/ADC12_IN7/TIM3_CH2_17") (pintype "passive"))
      (node (ref "R21") (pin "2") (pintype "passive"))
    )
    (net (code "60") (name "Net-(DD1-PA10{slash}USART1_RX{slash}TIM1_CH3)") (class "Default")
      (node (ref "DD1") (pin "31") (pinfunction "PA10/USART1_RX/TIM1_CH3_31") (pintype "passive"))
      (node (ref "TP6") (pin "1") (pintype "passive"))
    )
    (net (code "61") (name "Net-(DD1-VBAT)") (class "Default")
      (node (ref "DD1") (pin "1") (pinfunction "VBAT_1") (pintype "passive"))
      (node (ref "VD4") (pin "CA") (pintype "passive"))
    )
    (net (code "62") (name "Net-(FP2-Pad1)") (class "Default")
      (node (ref "FP2") (pin "1") (pintype "passive"))
      (node (ref "X2") (pin "3") (pinfunction "3_3") (pintype "passive"))
    )
    (net (code "63") (name "Net-(FP3-Pad1)") (class "Default")
      (node (ref "FP3") (pin "1") (pintype "passive"))
      (node (ref "X2") (pin "4") (pinfunction "4_4") (pintype "passive"))
    )
    (net (code "64") (name "Net-(HG2-Cathode)") (class "Default")
      (node (ref "HG2") (pin "CA") (pinfunction "Cathode_CA") (pintype "passive"))
      (node (ref "R24") (pin "2") (pintype "passive"))
    )
    (net (code "65") (name "Net-(PZ1-Negative)") (class "Default")
      (node (ref "PZ1") (pin "2") (pinfunction "Negative_2") (pintype "passive"))
      (node (ref "VT1") (pin "3") (pinfunction "C_3") (pintype "passive"))
    )
    (net (code "66") (name "Net-(PZ1-Positive)") (class "Default")
      (node (ref "PZ1") (pin "1") (pinfunction "Positive_1") (pintype "passive"))
      (node (ref "R20") (pin "1") (pintype "passive"))
    )
    (net (code "67") (name "Net-(R25-Pad2)") (class "Default")
      (node (ref "R25") (pin "2") (pintype "passive"))
      (node (ref "X5") (pin "3") (pinfunction "3_3") (pintype "passive"))
    )
    (net (code "68") (name "Net-(R26-Pad2)") (class "Default")
      (node (ref "R26") (pin "2") (pintype "passive"))
      (node (ref "X5") (pin "2") (pinfunction "2_2") (pintype "passive"))
    )
    (net (code "69") (name "Net-(VD1-Anode)") (class "Default")
      (node (ref "R23") (pin "1") (pintype "passive"))
      (node (ref "VD1") (pin "1") (pinfunction "Anode_1") (pintype "passive"))
    )
    (net (code "70") (name "unconnected-(D3-GPA0-Pad21)") (class "Default")
      (node (ref "D3") (pin "21") (pinfunction "GPA0_21") (pintype "passive"))
    )
    (net (code "71") (name "unconnected-(D3-GPA1-Pad22)") (class "Default")
      (node (ref "D3") (pin "22") (pinfunction "GPA1_22") (pintype "passive"))
    )
    (net (code "72") (name "unconnected-(D3-INTA-Pad20)") (class "Default")
      (node (ref "D3") (pin "20") (pinfunction "INTA_20") (pintype "passive+no_connect"))
    )
    (net (code "73") (name "unconnected-(D3-INTB-Pad19)") (class "Default")
      (node (ref "D3") (pin "19") (pinfunction "INTB_19") (pintype "passive+no_connect"))
    )
    (net (code "74") (name "unconnected-(D3-NC-Pad11)") (class "Default")
      (node (ref "D3") (pin "11") (pinfunction "NC_11") (pintype "passive+no_connect"))
    )
    (net (code "75") (name "unconnected-(D3-NC-Pad14)") (class "Default")
      (node (ref "D3") (pin "14") (pinfunction "NC_14") (pintype "passive+no_connect"))
    )
    (net (code "76") (name "unconnected-(DD1-OSC_OU~{T}PD1-Pad6)") (class "Default")
      (node (ref "DD1") (pin "6") (pinfunction "OSC_OU~{T}PD1_6") (pintype "passive"))
    )
    (net (code "77") (name "unconnected-(DD1-PA0{slash}WKUP{slash}USART2_CTS{slash}ADC12_IN0-Pad10)") (class "Default")
      (node (ref "DD1") (pin "10") (pinfunction "PA0/WKUP/USART2_CTS/ADC12_IN0_10") (pintype "passive"))
    )
  )
)
